# SCH_Manip_2024-06-24.net
KiCad netlist of a schematic drawn in EasyEDA
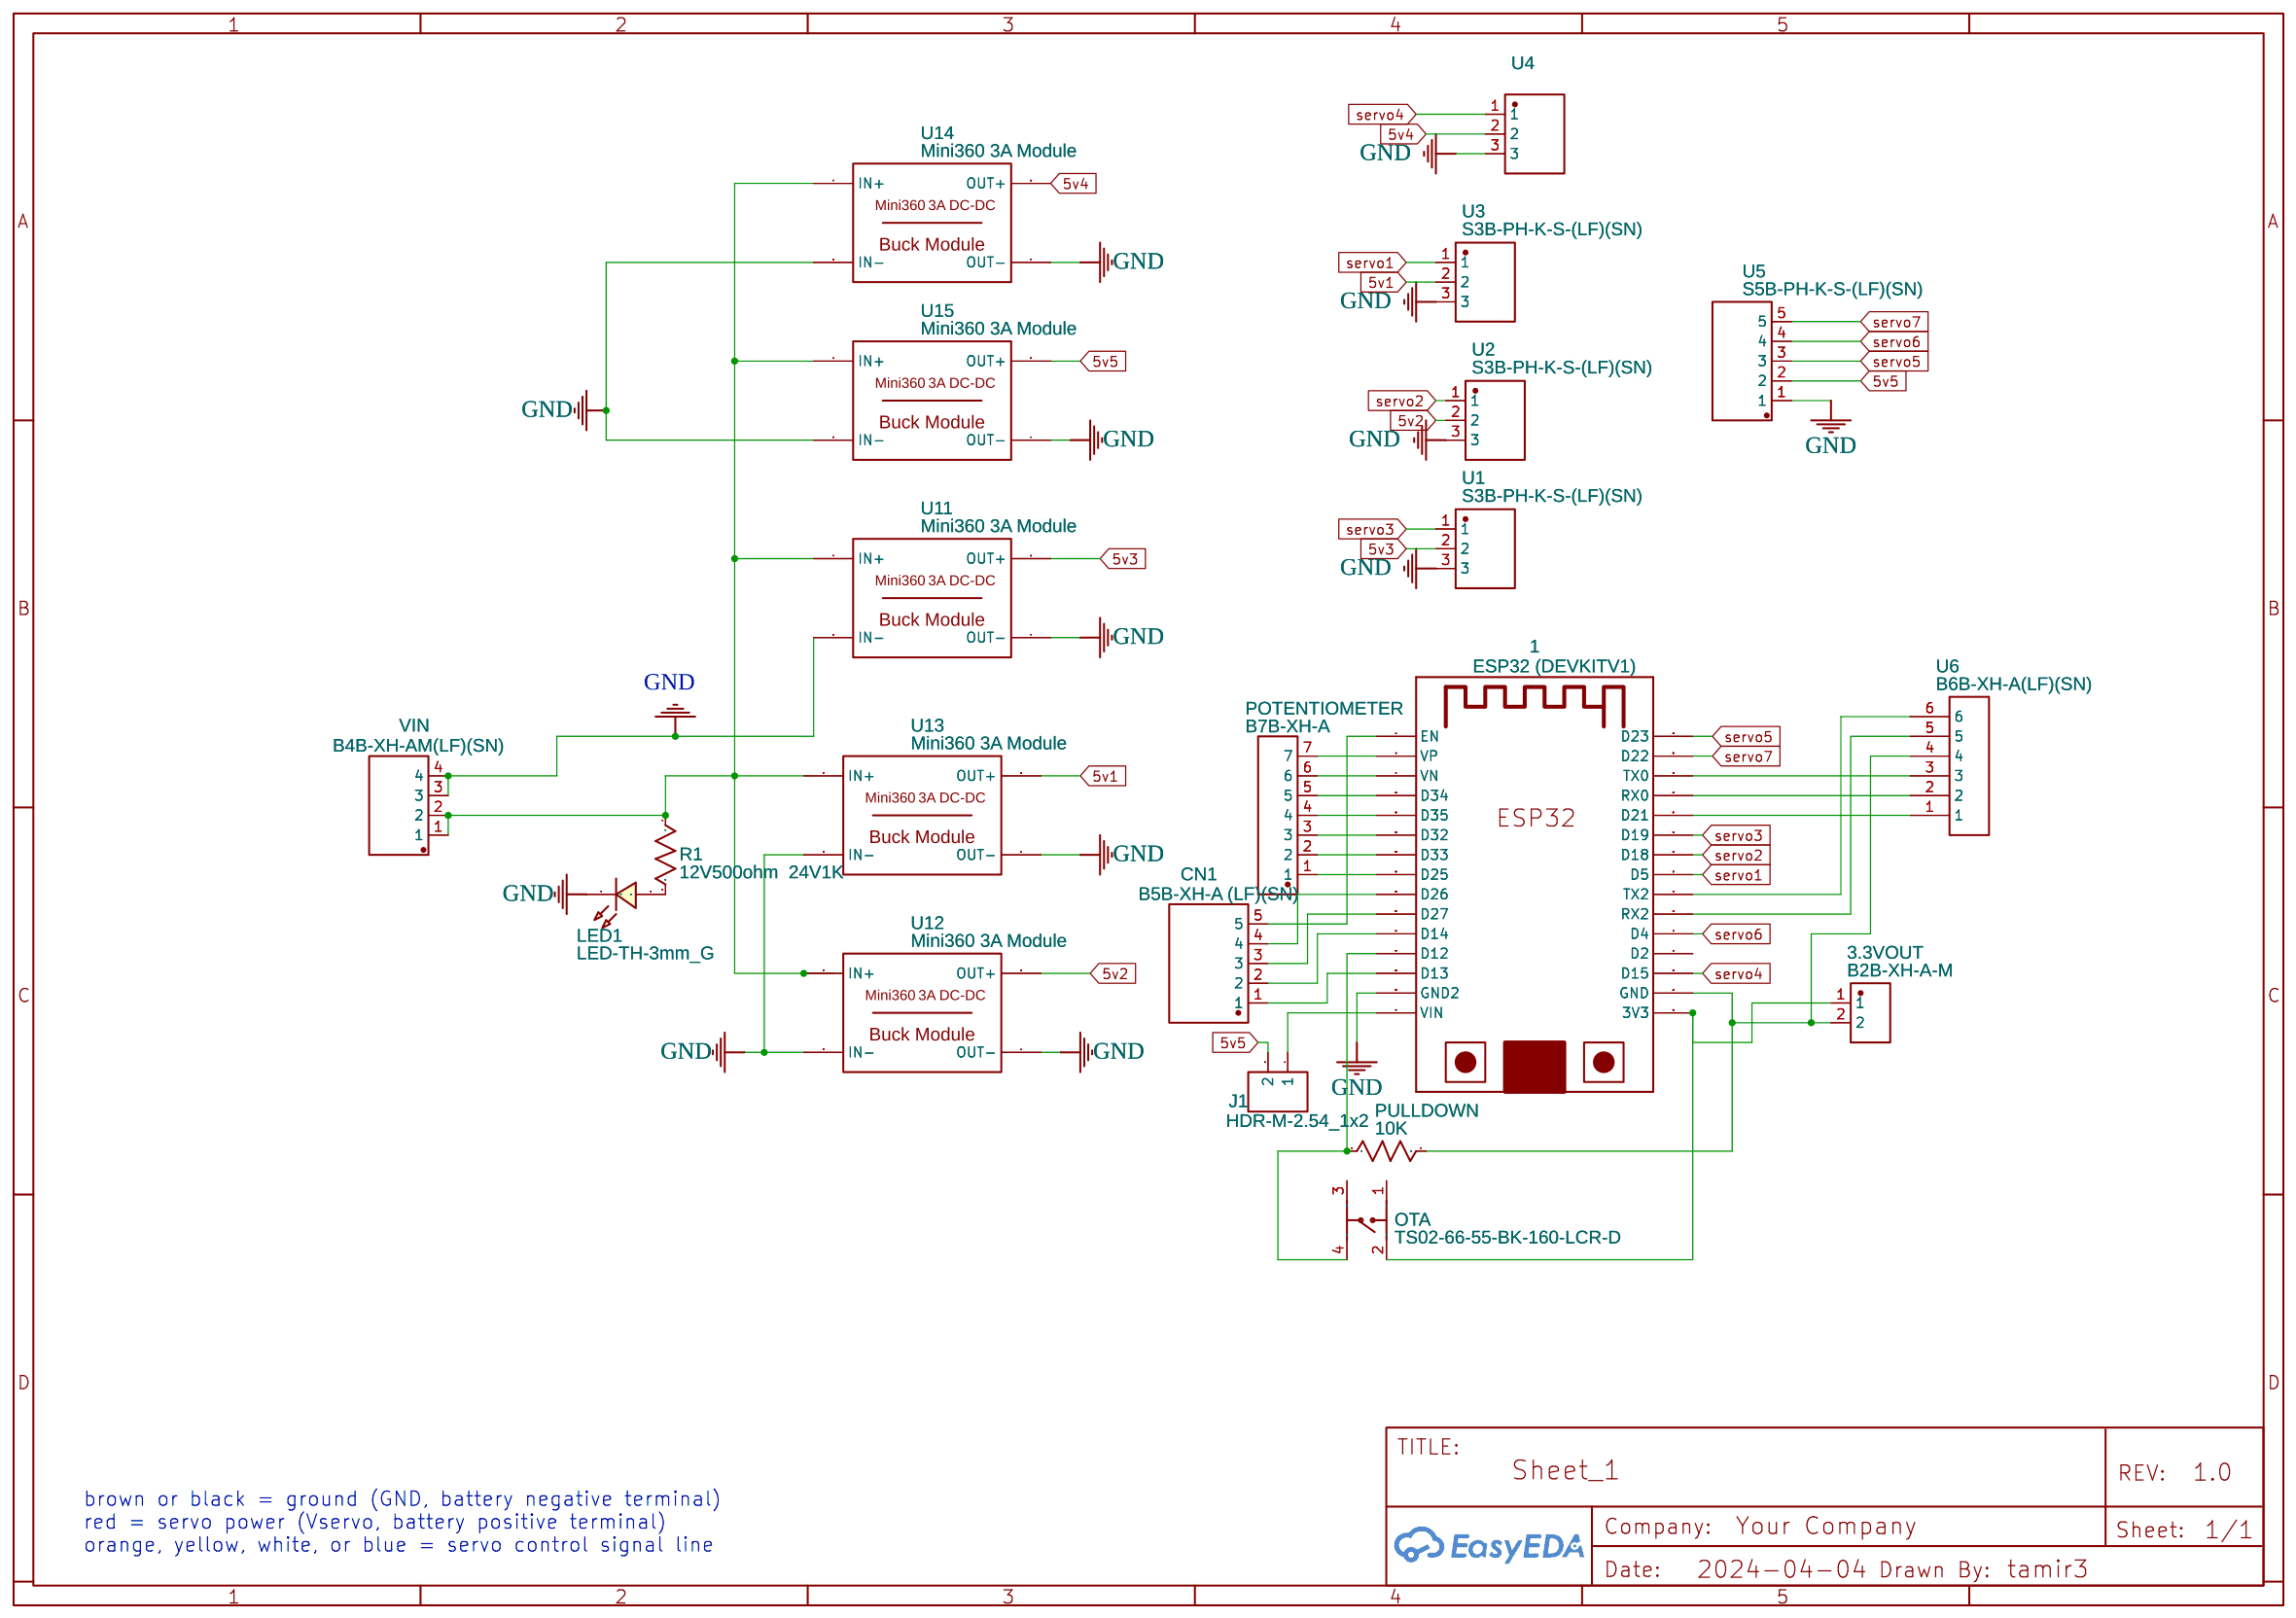
[diagram p0: schematic sheet]

(export (version "E")
  (design (tool "Eeschema 10.0.6"))
  (components
    (comp (ref "1") (value "ESP32 (DEVKITV1)") (libsource (lib "") (part "ESP32-DEVKIT-V1-30PIN")))
    (comp (ref "3.3VOUT")
      (value "B2B-XH-A-M")
      (fields (field (name "Manufacturer Part") "B2B-XH-A-MB2P-VH（SMT业务专用）"))
      (libsource (lib "") (part "B2B-XH-A-M"))
    )
    (comp (ref "CN1")
      (value "B5B-XH-A (LF)(SN)")
      (fields (field (name "Manufacturer Part") "B5B-XH-A(LF)(SN)") (field (name "Manufacturer") "JST"))
      (libsource (lib "") (part "B5B-XH-A (LF)(SN)"))
    )
    (comp (ref "J1") (value "HDR-M-2.54_1x2") (libsource (lib "") (part "HDR-M-2.54_1x2")))
    (comp (ref "LED1")
      (value "LED-TH-3mm_G")
      (fields
        (field (name "Manufacturer Part") "204-10SYGD/S530-E3")
        (field (name "Manufacturer") "EVERLIGHT(台湾亿光)")
      )
      (libsource (lib "") (part "LED-TH-3mm_G"))
    )
    (comp (ref "OTA")
      (value "TS02-66-55-BK-160-LCR-D")
      (fields (field (name "Manufacturer") "CUI"))
      (libsource (lib "") (part "TS02-66-55-BK-160-LCR-D"))
    )
    (comp (ref "POTENTIOMETER") (value "B7B-XH-A") (libsource (lib "") (part "B7B-XH-A")))
    (comp (ref "PULLDOWN") (value "10K") (libsource (lib "") (part "R_AXIAL-0.3_US")))
    (comp (ref "R1") (value "12V500ohm  24V1K") (libsource (lib "") (part "R_AXIAL-0.3_US_1")))
    (comp (ref "U1")
      (value "S3B-PH-K-S-(LF)(SN)")
      (fields (field (name "Manufacturer Part") "S3B-PH-K-S(LF)(SN)") (field (name "Manufacturer") "JST"))
      (libsource (lib "") (part "S3B-PH-K-S-(LF)(SN)"))
    )
    (comp (ref "U2")
      (value "S3B-PH-K-S-(LF)(SN)")
      (fields (field (name "Manufacturer Part") "S3B-PH-K-S(LF)(SN)") (field (name "Manufacturer") "JST"))
      (libsource (lib "") (part "S3B-PH-K-S-(LF)(SN)"))
    )
    (comp (ref "U3")
      (value "S3B-PH-K-S-(LF)(SN)")
      (fields (field (name "Manufacturer Part") "S3B-PH-K-S(LF)(SN)") (field (name "Manufacturer") "JST"))
      (libsource (lib "") (part "S3B-PH-K-S-(LF)(SN)"))
    )
    (comp (ref "U4")
      (value "S3B-PH-K-S-(LF)(SN)")
      (fields (field (name "Manufacturer Part") "S3B-PH-K-S(LF)(SN)") (field (name "Manufacturer") "JST"))
      (libsource (lib "") (part "S3B-PH-K-S-(LF)(SN)"))
    )
    (comp (ref "U5")
      (value "S5B-PH-K-S-(LF)(SN)")
      (fields (field (name "Manufacturer Part") "S5B-PH-K-S(LF)(SN)") (field (name "Manufacturer") "JST"))
      (libsource (lib "") (part "S5B-PH-K-S-(LF)(SN)"))
    )
    (comp (ref "U6")
      (value "B6B-XH-A(LF)(SN)")
      (fields (field (name "Manufacturer") "JST"))
      (libsource (lib "") (part "B6B-XH-A(LF)(SN)"))
    )
    (comp (ref "U11") (value "Mini360 3A Module") (libsource (lib "") (part "Mini360 3A Module")))
    (comp (ref "U12") (value "Mini360 3A Module") (libsource (lib "") (part "Mini360 3A Module")))
    (comp (ref "U13") (value "Mini360 3A Module") (libsource (lib "") (part "Mini360 3A Module")))
    (comp (ref "U14") (value "Mini360 3A Module") (libsource (lib "") (part "Mini360 3A Module")))
    (comp (ref "U15") (value "Mini360 3A Module") (libsource (lib "") (part "Mini360 3A Module")))
    (comp (ref "VIN")
      (value "B4B-XH-AM(LF)(SN)")
      (fields (field (name "Manufacturer") "JST"))
      (libsource (lib "") (part "B4B-XH-AM(LF)(SN)"))
    )
  )
  (nets
    (net (code "1") (name "5v1") (class "Default")
      (node (ref "U13") (pin "3") (pinfunction "OUT+_3") (pintype "unspecified"))
      (node (ref "U3") (pin "2") (pinfunction "2_2") (pintype "unspecified"))
    )
    (net (code "2") (name "5v2") (class "Default")
      (node (ref "U12") (pin "3") (pinfunction "OUT+_3") (pintype "unspecified"))
      (node (ref "U2") (pin "2") (pinfunction "2_2") (pintype "unspecified"))
    )
    (net (code "3") (name "5v3") (class "Default")
      (node (ref "U1") (pin "2") (pinfunction "2_2") (pintype "unspecified"))
      (node (ref "U11") (pin "3") (pinfunction "OUT+_3") (pintype "unspecified"))
    )
    (net (code "4") (name "5v4") (class "Default")
      (node (ref "U14") (pin "3") (pinfunction "OUT+_3") (pintype "unspecified"))
      (node (ref "U4") (pin "2") (pinfunction "2_2") (pintype "unspecified"))
    )
    (net (code "5") (name "5v5") (class "Default")
      (node (ref "J1") (pin "2") (pinfunction "2_2") (pintype "unspecified"))
      (node (ref "U15") (pin "3") (pinfunction "OUT+_3") (pintype "unspecified"))
      (node (ref "U5") (pin "2") (pinfunction "2_2") (pintype "unspecified"))
    )
    (net (code "6") (name "GND") (class "Default")
      (node (ref "1") (pin "GND2") (pinfunction "GND2_GND2") (pintype "unspecified"))
      (node (ref "LED1") (pin "2") (pinfunction "2_2") (pintype "unspecified"))
      (node (ref "U1") (pin "3") (pinfunction "3_3") (pintype "unspecified"))
      (node (ref "U11") (pin "2") (pinfunction "IN-_2") (pintype "unspecified"))
      (node (ref "U11") (pin "4") (pinfunction "OUT-_4") (pintype "unspecified"))
      (node (ref "U12") (pin "2") (pinfunction "IN-_2") (pintype "unspecified"))
      (node (ref "U12") (pin "4") (pinfunction "OUT-_4") (pintype "unspecified"))
      (node (ref "U13") (pin "2") (pinfunction "IN-_2") (pintype "unspecified"))
      (node (ref "U13") (pin "4") (pinfunction "OUT-_4") (pintype "unspecified"))
      (node (ref "U14") (pin "2") (pinfunction "IN-_2") (pintype "unspecified"))
      (node (ref "U14") (pin "4") (pinfunction "OUT-_4") (pintype "unspecified"))
      (node (ref "U15") (pin "2") (pinfunction "IN-_2") (pintype "unspecified"))
      (node (ref "U15") (pin "4") (pinfunction "OUT-_4") (pintype "unspecified"))
      (node (ref "U2") (pin "3") (pinfunction "3_3") (pintype "unspecified"))
      (node (ref "U3") (pin "3") (pinfunction "3_3") (pintype "unspecified"))
      (node (ref "U4") (pin "3") (pinfunction "3_3") (pintype "unspecified"))
      (node (ref "U5") (pin "1") (pinfunction "1_1") (pintype "unspecified"))
      (node (ref "VIN") (pin "3") (pinfunction "3_3") (pintype "unspecified"))
      (node (ref "VIN") (pin "4") (pinfunction "4_4") (pintype "unspecified"))
    )
    (net (code "7") (name "Net-(1-Pad3V3)") (class "Default")
      (node (ref "1") (pin "3V3") (pinfunction "3V3_3V3") (pintype "unspecified"))
      (node (ref "3.3VOUT") (pin "1") (pinfunction "1_1") (pintype "unspecified"))
      (node (ref "OTA") (pin "2") (pinfunction "2_2") (pintype "unspecified"))
    )
    (net (code "8") (name "Net-(1-PadD12)") (class "Default")
      (node (ref "1") (pin "D12") (pinfunction "D12_D12") (pintype "unspecified"))
      (node (ref "OTA") (pin "4") (pinfunction "4_4") (pintype "unspecified"))
      (node (ref "PULLDOWN") (pin "1") (pinfunction "1_1") (pintype "unspecified"))
    )
    (net (code "9") (name "Net-(1-PadD13)") (class "Default")
      (node (ref "1") (pin "D13") (pinfunction "D13_D13") (pintype "unspecified"))
      (node (ref "CN1") (pin "1") (pinfunction "1_1") (pintype "unspecified"))
    )
    (net (code "10") (name "Net-(1-PadD14)") (class "Default")
      (node (ref "1") (pin "D14") (pinfunction "D14_D14") (pintype "unspecified"))
      (node (ref "CN1") (pin "2") (pinfunction "2_2") (pintype "unspecified"))
    )
    (net (code "11") (name "Net-(1-PadD21)") (class "Default")
      (node (ref "1") (pin "D21") (pinfunction "D21_D21") (pintype "unspecified"))
      (node (ref "U6") (pin "1") (pinfunction "1_1") (pintype "unspecified"))
    )
    (net (code "12") (name "Net-(1-PadD25)") (class "Default")
      (node (ref "1") (pin "D25") (pinfunction "D25_D25") (pintype "unspecified"))
      (node (ref "POTENTIOMETER") (pin "1") (pinfunction "1_1") (pintype "unspecified"))
    )
    (net (code "13") (name "Net-(1-PadD26)") (class "Default")
      (node (ref "1") (pin "D26") (pinfunction "D26_D26") (pintype "unspecified"))
      (node (ref "CN1") (pin "4") (pinfunction "4_4") (pintype "unspecified"))
    )
    (net (code "14") (name "Net-(1-PadD27)") (class "Default")
      (node (ref "1") (pin "D27") (pinfunction "D27_D27") (pintype "unspecified"))
      (node (ref "CN1") (pin "3") (pinfunction "3_3") (pintype "unspecified"))
    )
    (net (code "15") (name "Net-(1-PadD32)") (class "Default")
      (node (ref "1") (pin "D32") (pinfunction "D32_D32") (pintype "unspecified"))
      (node (ref "POTENTIOMETER") (pin "3") (pinfunction "3_3") (pintype "unspecified"))
    )
    (net (code "16") (name "Net-(1-PadD33)") (class "Default")
      (node (ref "1") (pin "D33") (pinfunction "D33_D33") (pintype "unspecified"))
      (node (ref "POTENTIOMETER") (pin "2") (pinfunction "2_2") (pintype "unspecified"))
    )
    (net (code "17") (name "Net-(1-PadD34)") (class "Default")
      (node (ref "1") (pin "D34") (pinfunction "D34_D34") (pintype "unspecified"))
      (node (ref "POTENTIOMETER") (pin "5") (pinfunction "5_5") (pintype "unspecified"))
    )
    (net (code "18") (name "Net-(1-PadD35)") (class "Default")
      (node (ref "1") (pin "D35") (pinfunction "D35_D35") (pintype "unspecified"))
      (node (ref "POTENTIOMETER") (pin "4") (pinfunction "4_4") (pintype "unspecified"))
    )
    (net (code "19") (name "Net-(1-PadEN)") (class "Default")
      (node (ref "1") (pin "EN") (pinfunction "EN_EN") (pintype "unspecified"))
      (node (ref "CN1") (pin "5") (pinfunction "5_5") (pintype "unspecified"))
    )
    (net (code "20") (name "Net-(1-PadGND)") (class "Default")
      (node (ref "1") (pin "GND") (pinfunction "GND_GND") (pintype "unspecified"))
      (node (ref "3.3VOUT") (pin "2") (pinfunction "2_2") (pintype "unspecified"))
      (node (ref "PULLDOWN") (pin "2") (pinfunction "2_2") (pintype "unspecified"))
      (node (ref "U6") (pin "4") (pinfunction "4_4") (pintype "unspecified"))
    )
    (net (code "21") (name "Net-(1-PadRX0)") (class "Default")
      (node (ref "1") (pin "RX0") (pinfunction "RX0_RX0") (pintype "unspecified"))
      (node (ref "U6") (pin "2") (pinfunction "2_2") (pintype "unspecified"))
    )
    (net (code "22") (name "Net-(1-PadRX2)") (class "Default")
      (node (ref "1") (pin "RX2") (pinfunction "RX2_RX2") (pintype "unspecified"))
      (node (ref "U6") (pin "5") (pinfunction "5_5") (pintype "unspecified"))
    )
    (net (code "23") (name "Net-(1-PadTX0)") (class "Default")
      (node (ref "1") (pin "TX0") (pinfunction "TX0_TX0") (pintype "unspecified"))
      (node (ref "U6") (pin "3") (pinfunction "3_3") (pintype "unspecified"))
    )
    (net (code "24") (name "Net-(1-PadTX2)") (class "Default")
      (node (ref "1") (pin "TX2") (pinfunction "TX2_TX2") (pintype "unspecified"))
      (node (ref "U6") (pin "6") (pinfunction "6_6") (pintype "unspecified"))
    )
    (net (code "25") (name "Net-(1-PadVIN)") (class "Default")
      (node (ref "1") (pin "VIN") (pinfunction "VIN_VIN") (pintype "unspecified"))
      (node (ref "J1") (pin "1") (pinfunction "1_1") (pintype "unspecified"))
    )
    (net (code "26") (name "Net-(1-PadVN)") (class "Default")
      (node (ref "1") (pin "VN") (pinfunction "VN_VN") (pintype "unspecified"))
      (node (ref "POTENTIOMETER") (pin "6") (pinfunction "6_6") (pintype "unspecified"))
    )
    (net (code "27") (name "Net-(1-PadVP)") (class "Default")
      (node (ref "1") (pin "VP") (pinfunction "VP_VP") (pintype "unspecified"))
      (node (ref "POTENTIOMETER") (pin "7") (pinfunction "7_7") (pintype "unspecified"))
    )
    (net (code "28") (name "Net-(LED1-Pad1)") (class "Default")
      (node (ref "LED1") (pin "1") (pinfunction "1_1") (pintype "unspecified"))
      (node (ref "R1") (pin "2") (pinfunction "2_2") (pintype "unspecified"))
    )
    (net (code "29") (name "Net-(U11-IN+)") (class "Default")
      (node (ref "R1") (pin "1") (pinfunction "1_1") (pintype "unspecified"))
      (node (ref "U11") (pin "1") (pinfunction "IN+_1") (pintype "unspecified"))
      (node (ref "U12") (pin "1") (pinfunction "IN+_1") (pintype "unspecified"))
      (node (ref "U13") (pin "1") (pinfunction "IN+_1") (pintype "unspecified"))
      (node (ref "U14") (pin "1") (pinfunction "IN+_1") (pintype "unspecified"))
      (node (ref "U15") (pin "1") (pinfunction "IN+_1") (pintype "unspecified"))
      (node (ref "VIN") (pin "1") (pinfunction "1_1") (pintype "unspecified"))
      (node (ref "VIN") (pin "2") (pinfunction "2_2") (pintype "unspecified"))
    )
    (net (code "30") (name "servo1") (class "Default")
      (node (ref "1") (pin "D5") (pinfunction "D5_D5") (pintype "unspecified"))
      (node (ref "U3") (pin "1") (pinfunction "1_1") (pintype "unspecified"))
    )
    (net (code "31") (name "servo2") (class "Default")
      (node (ref "1") (pin "D18") (pinfunction "D18_D18") (pintype "unspecified"))
      (node (ref "U2") (pin "1") (pinfunction "1_1") (pintype "unspecified"))
    )
    (net (code "32") (name "servo3") (class "Default")
      (node (ref "1") (pin "D19") (pinfunction "D19_D19") (pintype "unspecified"))
      (node (ref "U1") (pin "1") (pinfunction "1_1") (pintype "unspecified"))
    )
    (net (code "33") (name "servo4") (class "Default")
      (node (ref "1") (pin "D15") (pinfunction "D15_D15") (pintype "unspecified"))
      (node (ref "U4") (pin "1") (pinfunction "1_1") (pintype "unspecified"))
    )
    (net (code "34") (name "servo5") (class "Default")
      (node (ref "1") (pin "D23") (pinfunction "D23_D23") (pintype "unspecified"))
      (node (ref "U5") (pin "3") (pinfunction "3_3") (pintype "unspecified"))
    )
    (net (code "35") (name "servo6") (class "Default")
      (node (ref "1") (pin "D4") (pinfunction "D4_D4") (pintype "unspecified"))
      (node (ref "U5") (pin "4") (pinfunction "4_4") (pintype "unspecified"))
    )
    (net (code "36") (name "servo7") (class "Default")
      (node (ref "1") (pin "D22") (pinfunction "D22_D22") (pintype "unspecified"))
      (node (ref "U5") (pin "5") (pinfunction "5_5") (pintype "unspecified"))
    )
    (net (code "37") (name "unconnected-(1-PadD2)") (class "Default")
      (node (ref "1") (pin "D2") (pinfunction "D2_D2") (pintype "unspecified"))
    )
    (net (code "38") (name "unconnected-(OTA-Pad1)") (class "Default")
      (node (ref "OTA") (pin "1") (pinfunction "1_1") (pintype "unspecified"))
    )
    (net (code "39") (name "unconnected-(OTA-Pad3)") (class "Default")
      (node (ref "OTA") (pin "3") (pinfunction "3_3") (pintype "unspecified"))
    )
  )
)
